# SUSTAINA-SBC-Power-Board.net
KiCad netlist of a schematic drawn in EAGLE
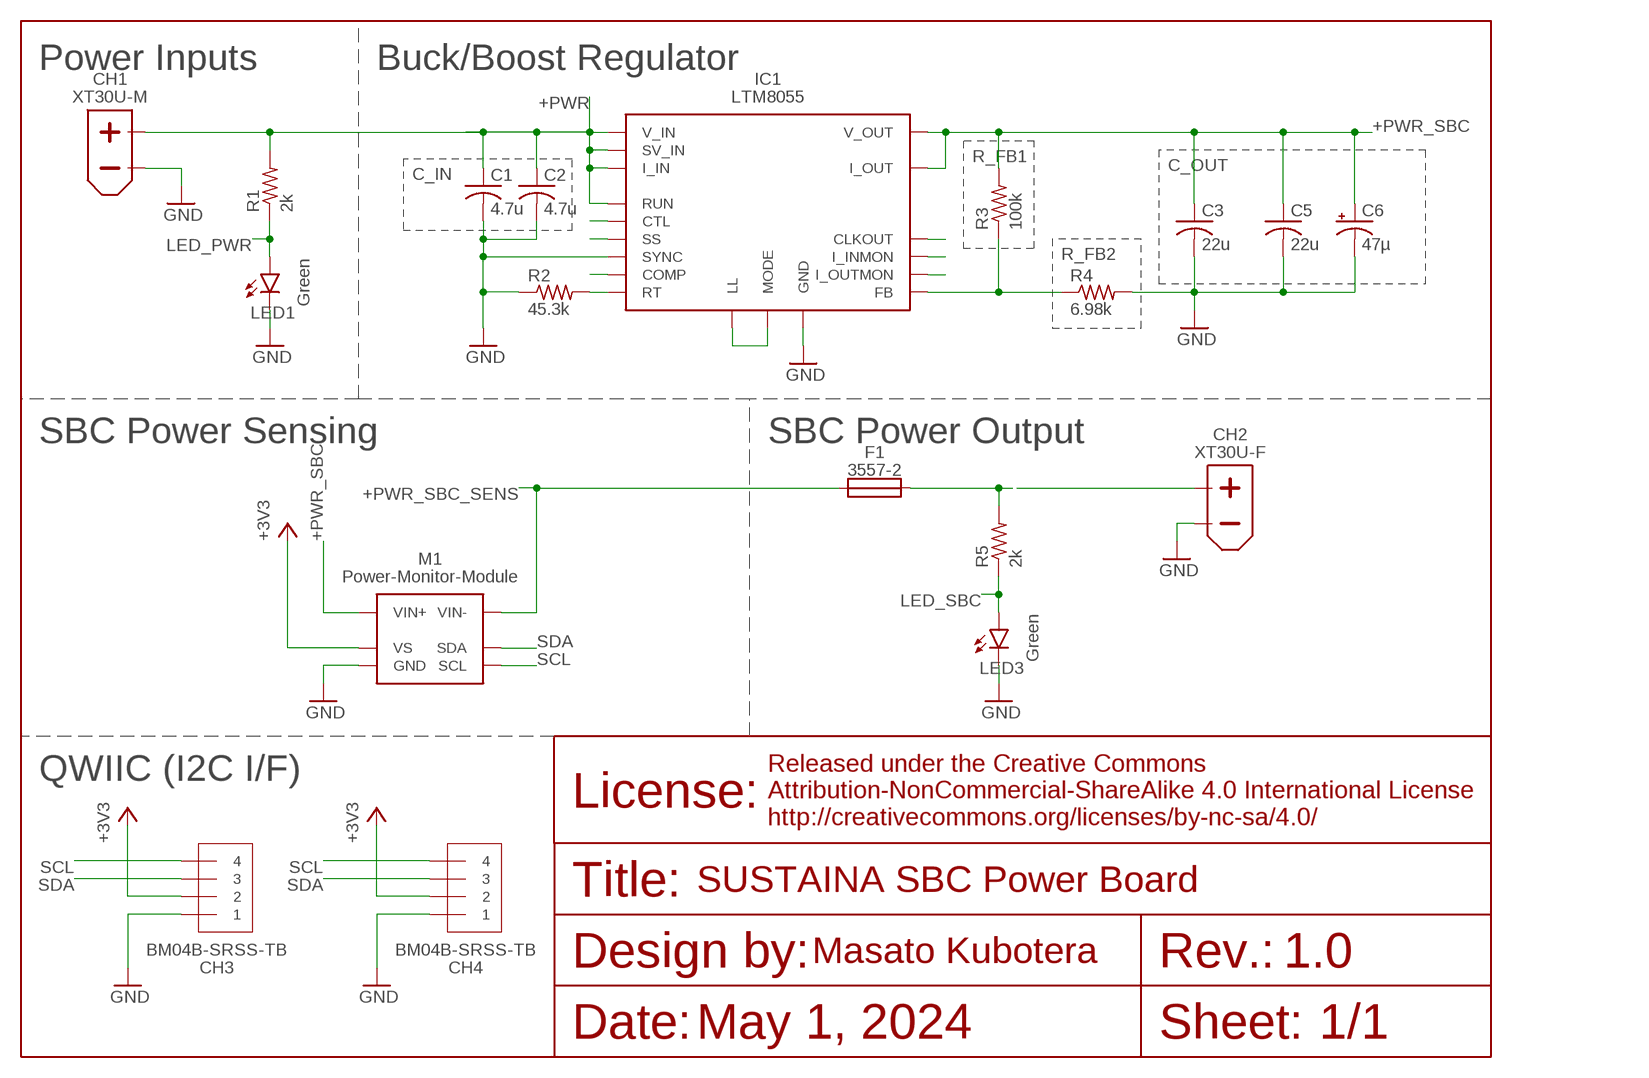
[diagram p0: schematic, sheet 1]

(export (version "E")
  (design (tool "Eeschema 10.0.6"))
  (components
    (comp (ref "C1")
      (value "4.7u")
      (footprint "eagle-import:C0805")
      (libsource (lib "eagle-import") (part "C-USC0805"))
    )
    (comp (ref "C2")
      (value "4.7u")
      (footprint "eagle-import:C0805")
      (libsource (lib "eagle-import") (part "C-USC0805"))
    )
    (comp (ref "C3")
      (value "22u")
      (footprint "eagle-import:C0805")
      (libsource (lib "eagle-import") (part "C-USC0805"))
    )
    (comp (ref "C5")
      (value "22u")
      (footprint "eagle-import:C0805")
      (libsource (lib "eagle-import") (part "C-USC0805"))
    )
    (comp (ref "C6")
      (value "47µ")
      (footprint "eagle-import:D_7343-31R")
      (libsource (lib "eagle-import") (part "CPOL-USD/7343-31R"))
    )
    (comp (ref "CH1")
      (value "XT30U-M")
      (footprint "eagle-import:XT30U-M")
      (libsource (lib "eagle-import") (part "XT30U-M"))
    )
    (comp (ref "CH2")
      (value "XT30U-F")
      (footprint "eagle-import:XT30U-F")
      (libsource (lib "eagle-import") (part "XT30U-F"))
    )
    (comp (ref "CH3")
      (value "BM04B-SRSS-TB")
      (footprint "eagle-import:BM04B-SRSS-TB")
      (libsource (lib "eagle-import") (part "BM04B-SRSS-TB"))
    )
    (comp (ref "CH4")
      (value "BM04B-SRSS-TB")
      (footprint "eagle-import:BM04B-SRSS-TB")
      (libsource (lib "eagle-import") (part "BM04B-SRSS-TB"))
    )
    (comp (ref "F1")
      (value "3557-2")
      (footprint "eagle-import:3557-2")
      (libsource (lib "eagle-import") (part "3557-2"))
    )
    (comp (ref "IC1")
      (value "LTM8055")
      (footprint "eagle-import:LTM8055")
      (libsource (lib "eagle-import") (part "LTM8055"))
    )
    (comp (ref "LED1")
      (value "Green")
      (footprint "eagle-import:SML0603")
      (libsource (lib "eagle-import") (part "LEDSML0603"))
    )
    (comp (ref "LED3")
      (value "Green")
      (footprint "eagle-import:SML0603")
      (libsource (lib "eagle-import") (part "LEDSML0603"))
    )
    (comp (ref "M1")
      (value "POWER-MONITOR-MODULE")
      (footprint "eagle-import:POWER-MONITOR-MODULE")
      (libsource (lib "eagle-import") (part "POWER-MONITOR-MODULE"))
    )
    (comp (ref "R1")
      (value "2k")
      (footprint "eagle-import:R0603")
      (libsource (lib "eagle-import") (part "R-US_R0603"))
    )
    (comp (ref "R2")
      (value "45.3k")
      (footprint "eagle-import:R0603")
      (libsource (lib "eagle-import") (part "R-US_R0603"))
    )
    (comp (ref "R3")
      (value "100k")
      (footprint "eagle-import:R0603")
      (libsource (lib "eagle-import") (part "R-US_R0603"))
    )
    (comp (ref "R4")
      (value "6.98k")
      (footprint "eagle-import:R0603")
      (libsource (lib "eagle-import") (part "R-US_R0603"))
    )
    (comp (ref "R5")
      (value "2k")
      (footprint "eagle-import:R0603")
      (libsource (lib "eagle-import") (part "R-US_R0603"))
    )
  )
  (nets
    (net (code "1") (name "+3V3") (class "Default")
      (node (ref "CH3") (pin "2") (pinfunction "2_2") (pintype "bidirectional"))
      (node (ref "CH4") (pin "2") (pinfunction "2_2") (pintype "bidirectional"))
      (node (ref "M1") (pin "VS") (pinfunction "VS_VS") (pintype "power_in"))
    )
    (net (code "2") (name "/+PWR") (class "Default")
      (node (ref "C1") (pin "1") (pinfunction "1_1") (pintype "passive"))
      (node (ref "C2") (pin "1") (pinfunction "1_1") (pintype "passive"))
      (node (ref "CH1") (pin "+") (pinfunction "+_+") (pintype "power_in"))
      (node (ref "IC1") (pin "F10") (pinfunction "SV_IN_F10") (pintype "bidirectional"))
      (node (ref "IC1") (pin "F11") (pinfunction "SV_IN_F11") (pintype "bidirectional"))
      (node (ref "IC1") (pin "G10") (pinfunction "V_IN_G10") (pintype "bidirectional"))
      (node (ref "IC1") (pin "G11") (pinfunction "V_IN_G11") (pintype "bidirectional"))
      (node (ref "IC1") (pin "H10") (pinfunction "V_IN_H10") (pintype "bidirectional"))
      (node (ref "IC1") (pin "H11") (pinfunction "V_IN_H11") (pintype "bidirectional"))
      (node (ref "IC1") (pin "J10") (pinfunction "V_IN_J10") (pintype "bidirectional"))
      (node (ref "IC1") (pin "J11") (pinfunction "V_IN_J11") (pintype "bidirectional"))
      (node (ref "IC1") (pin "K10") (pinfunction "V_IN_K10") (pintype "bidirectional"))
      (node (ref "IC1") (pin "K11") (pinfunction "V_IN_K11") (pintype "bidirectional"))
      (node (ref "IC1") (pin "L10") (pinfunction "V_IN_L10") (pintype "bidirectional"))
      (node (ref "IC1") (pin "L11") (pinfunction "V_IN_L11") (pintype "bidirectional"))
      (node (ref "IC1") (pin "L4") (pinfunction "RUN_L4") (pintype "bidirectional"))
      (node (ref "IC1") (pin "L9") (pinfunction "I_IN_L9") (pintype "bidirectional"))
      (node (ref "R1") (pin "2") (pinfunction "2_2") (pintype "passive"))
    )
    (net (code "3") (name "/+PWR_SBC") (class "Default")
      (node (ref "C3") (pin "1") (pinfunction "1_1") (pintype "passive"))
      (node (ref "C5") (pin "1") (pinfunction "1_1") (pintype "passive"))
      (node (ref "C6") (pin "+") (pinfunction "+_+") (pintype "passive"))
      (node (ref "IC1") (pin "A1") (pinfunction "V_OUT_A1") (pintype "bidirectional"))
      (node (ref "IC1") (pin "A2") (pinfunction "V_OUT_A2") (pintype "bidirectional"))
      (node (ref "IC1") (pin "A3") (pinfunction "V_OUT_A3") (pintype "bidirectional"))
      (node (ref "IC1") (pin "A4") (pinfunction "V_OUT_A4") (pintype "bidirectional"))
      (node (ref "IC1") (pin "A5") (pinfunction "V_OUT_A5") (pintype "bidirectional"))
      (node (ref "IC1") (pin "A6") (pinfunction "V_OUT_A6") (pintype "bidirectional"))
      (node (ref "IC1") (pin "B1") (pinfunction "V_OUT_B1") (pintype "bidirectional"))
      (node (ref "IC1") (pin "B2") (pinfunction "V_OUT_B2") (pintype "bidirectional"))
      (node (ref "IC1") (pin "B3") (pinfunction "V_OUT_B3") (pintype "bidirectional"))
      (node (ref "IC1") (pin "B4") (pinfunction "V_OUT_B4") (pintype "bidirectional"))
      (node (ref "IC1") (pin "B5") (pinfunction "V_OUT_B5") (pintype "bidirectional"))
      (node (ref "IC1") (pin "B6") (pinfunction "V_OUT_B6") (pintype "bidirectional"))
      (node (ref "IC1") (pin "C1") (pinfunction "V_OUT_C1") (pintype "bidirectional"))
      (node (ref "IC1") (pin "C2") (pinfunction "V_OUT_C2") (pintype "bidirectional"))
      (node (ref "IC1") (pin "C3") (pinfunction "V_OUT_C3") (pintype "bidirectional"))
      (node (ref "IC1") (pin "C4") (pinfunction "V_OUT_C4") (pintype "bidirectional"))
      (node (ref "IC1") (pin "C5") (pinfunction "V_OUT_C5") (pintype "bidirectional"))
      (node (ref "IC1") (pin "C6") (pinfunction "V_OUT_C6") (pintype "bidirectional"))
      (node (ref "IC1") (pin "D1") (pinfunction "I_OUT_D1") (pintype "bidirectional"))
      (node (ref "M1") (pin "VIN+1") (pinfunction "VIN+_VIN+1") (pintype "power_in"))
      (node (ref "M1") (pin "VIN+10") (pinfunction "VIN+_VIN+10") (pintype "power_in"))
      (node (ref "M1") (pin "VIN+2") (pinfunction "VIN+_VIN+2") (pintype "power_in"))
      (node (ref "M1") (pin "VIN+3") (pinfunction "VIN+_VIN+3") (pintype "power_in"))
      (node (ref "M1") (pin "VIN+4") (pinfunction "VIN+_VIN+4") (pintype "power_in"))
      (node (ref "M1") (pin "VIN+5") (pinfunction "VIN+_VIN+5") (pintype "power_in"))
      (node (ref "M1") (pin "VIN+6") (pinfunction "VIN+_VIN+6") (pintype "power_in"))
      (node (ref "M1") (pin "VIN+7") (pinfunction "VIN+_VIN+7") (pintype "power_in"))
      (node (ref "M1") (pin "VIN+8") (pinfunction "VIN+_VIN+8") (pintype "power_in"))
      (node (ref "M1") (pin "VIN+9") (pinfunction "VIN+_VIN+9") (pintype "power_in"))
      (node (ref "R3") (pin "2") (pinfunction "2_2") (pintype "passive"))
    )
    (net (code "4") (name "/+PWR_SBC_SENS") (class "Default")
      (node (ref "F1") (pin "1") (pinfunction "1_1") (pintype "bidirectional"))
      (node (ref "F1") (pin "2") (pinfunction "1_2") (pintype "bidirectional"))
      (node (ref "M1") (pin "VIN-1") (pinfunction "VIN-_VIN-1") (pintype "power_in"))
      (node (ref "M1") (pin "VIN-10") (pinfunction "VIN-_VIN-10") (pintype "power_in"))
      (node (ref "M1") (pin "VIN-2") (pinfunction "VIN-_VIN-2") (pintype "power_in"))
      (node (ref "M1") (pin "VIN-3") (pinfunction "VIN-_VIN-3") (pintype "power_in"))
      (node (ref "M1") (pin "VIN-4") (pinfunction "VIN-_VIN-4") (pintype "power_in"))
      (node (ref "M1") (pin "VIN-5") (pinfunction "VIN-_VIN-5") (pintype "power_in"))
      (node (ref "M1") (pin "VIN-6") (pinfunction "VIN-_VIN-6") (pintype "power_in"))
      (node (ref "M1") (pin "VIN-7") (pinfunction "VIN-_VIN-7") (pintype "power_in"))
      (node (ref "M1") (pin "VIN-8") (pinfunction "VIN-_VIN-8") (pintype "power_in"))
      (node (ref "M1") (pin "VIN-9") (pinfunction "VIN-_VIN-9") (pintype "power_in"))
    )
    (net (code "5") (name "/LED_PWR") (class "Default")
      (node (ref "LED1") (pin "A") (pinfunction "A_A") (pintype "passive"))
      (node (ref "R1") (pin "1") (pinfunction "1_1") (pintype "passive"))
    )
    (net (code "6") (name "/LED_SBC") (class "Default")
      (node (ref "LED3") (pin "A") (pinfunction "A_A") (pintype "passive"))
      (node (ref "R5") (pin "1") (pinfunction "1_1") (pintype "passive"))
    )
    (net (code "7") (name "/SCL") (class "Default")
      (node (ref "CH3") (pin "4") (pinfunction "4_4") (pintype "bidirectional"))
      (node (ref "CH4") (pin "4") (pinfunction "4_4") (pintype "bidirectional"))
      (node (ref "M1") (pin "SCL") (pinfunction "SCL_SCL") (pintype "bidirectional"))
    )
    (net (code "8") (name "/SDA") (class "Default")
      (node (ref "CH3") (pin "3") (pinfunction "3_3") (pintype "bidirectional"))
      (node (ref "CH4") (pin "3") (pinfunction "3_3") (pintype "bidirectional"))
      (node (ref "M1") (pin "SDA") (pinfunction "SDA_SDA") (pintype "bidirectional"))
    )
    (net (code "9") (name "GND") (class "Default")
      (node (ref "C1") (pin "2") (pinfunction "2_2") (pintype "passive"))
      (node (ref "C2") (pin "2") (pinfunction "2_2") (pintype "passive"))
      (node (ref "C3") (pin "2") (pinfunction "2_2") (pintype "passive"))
      (node (ref "C5") (pin "2") (pinfunction "2_2") (pintype "passive"))
      (node (ref "C6") (pin "-") (pinfunction "-_-") (pintype "passive"))
      (node (ref "CH1") (pin "-") (pinfunction "-_-") (pintype "power_in"))
      (node (ref "CH2") (pin "-") (pinfunction "-_-") (pintype "power_in"))
      (node (ref "CH3") (pin "1") (pinfunction "1_1") (pintype "bidirectional"))
      (node (ref "CH4") (pin "1") (pinfunction "1_1") (pintype "bidirectional"))
      (node (ref "IC1") (pin "A10") (pinfunction "GND_A10") (pintype "bidirectional"))
      (node (ref "IC1") (pin "A11") (pinfunction "GND_A11") (pintype "bidirectional"))
      (node (ref "IC1") (pin "A7") (pinfunction "GND_A7") (pintype "bidirectional"))
      (node (ref "IC1") (pin "A8") (pinfunction "GND_A8") (pintype "bidirectional"))
      (node (ref "IC1") (pin "A9") (pinfunction "GND_A9") (pintype "bidirectional"))
      (node (ref "IC1") (pin "B10") (pinfunction "GND_B10") (pintype "bidirectional"))
      (node (ref "IC1") (pin "B11") (pinfunction "GND_B11") (pintype "bidirectional"))
      (node (ref "IC1") (pin "B7") (pinfunction "GND_B7") (pintype "bidirectional"))
      (node (ref "IC1") (pin "B8") (pinfunction "GND_B8") (pintype "bidirectional"))
      (node (ref "IC1") (pin "B9") (pinfunction "GND_B9") (pintype "bidirectional"))
      (node (ref "IC1") (pin "C10") (pinfunction "GND_C10") (pintype "bidirectional"))
      (node (ref "IC1") (pin "C11") (pinfunction "GND_C11") (pintype "bidirectional"))
      (node (ref "IC1") (pin "C7") (pinfunction "GND_C7") (pintype "bidirectional"))
      (node (ref "IC1") (pin "C8") (pinfunction "GND_C8") (pintype "bidirectional"))
      (node (ref "IC1") (pin "C9") (pinfunction "GND_C9") (pintype "bidirectional"))
      (node (ref "IC1") (pin "D10") (pinfunction "GND_D10") (pintype "bidirectional"))
      (node (ref "IC1") (pin "D11") (pinfunction "GND_D11") (pintype "bidirectional"))
      (node (ref "IC1") (pin "D2") (pinfunction "GND_D2") (pintype "bidirectional"))
      (node (ref "IC1") (pin "D3") (pinfunction "GND_D3") (pintype "bidirectional"))
      (node (ref "IC1") (pin "D4") (pinfunction "GND_D4") (pintype "bidirectional"))
      (node (ref "IC1") (pin "D5") (pinfunction "GND_D5") (pintype "bidirectional"))
      (node (ref "IC1") (pin "D6") (pinfunction "GND_D6") (pintype "bidirectional"))
      (node (ref "IC1") (pin "D7") (pinfunction "GND_D7") (pintype "bidirectional"))
      (node (ref "IC1") (pin "D8") (pinfunction "GND_D8") (pintype "bidirectional"))
      (node (ref "IC1") (pin "D9") (pinfunction "GND_D9") (pintype "bidirectional"))
      (node (ref "IC1") (pin "E1") (pinfunction "GND_E1") (pintype "bidirectional"))
      (node (ref "IC1") (pin "E10") (pinfunction "GND_E10") (pintype "bidirectional"))
      (node (ref "IC1") (pin "E11") (pinfunction "GND_E11") (pintype "bidirectional"))
      (node (ref "IC1") (pin "E2") (pinfunction "GND_E2") (pintype "bidirectional"))
      (node (ref "IC1") (pin "E3") (pinfunction "GND_E3") (pintype "bidirectional"))
      (node (ref "IC1") (pin "E4") (pinfunction "GND_E4") (pintype "bidirectional"))
      (node (ref "IC1") (pin "E5") (pinfunction "GND_E5") (pintype "bidirectional"))
      (node (ref "IC1") (pin "E6") (pinfunction "GND_E6") (pintype "bidirectional"))
      (node (ref "IC1") (pin "E7") (pinfunction "GND_E7") (pintype "bidirectional"))
      (node (ref "IC1") (pin "E8") (pinfunction "GND_E8") (pintype "bidirectional"))
      (node (ref "IC1") (pin "E9") (pinfunction "GND_E9") (pintype "bidirectional"))
      (node (ref "IC1") (pin "F2") (pinfunction "GND_F2") (pintype "bidirectional"))
      (node (ref "IC1") (pin "F3") (pinfunction "GND_F3") (pintype "bidirectional"))
      (node (ref "IC1") (pin "F4") (pinfunction "GND_F4") (pintype "bidirectional"))
      (node (ref "IC1") (pin "F5") (pinfunction "GND_F5") (pintype "bidirectional"))
      (node (ref "IC1") (pin "F6") (pinfunction "GND_F6") (pintype "bidirectional"))
      (node (ref "IC1") (pin "F7") (pinfunction "GND_F7") (pintype "bidirectional"))
      (node (ref "IC1") (pin "F8") (pinfunction "GND_F8") (pintype "bidirectional"))
      (node (ref "IC1") (pin "F9") (pinfunction "GND_F9") (pintype "bidirectional"))
      (node (ref "IC1") (pin "G3") (pinfunction "GND_G3") (pintype "bidirectional"))
      (node (ref "IC1") (pin "G4") (pinfunction "GND_G4") (pintype "bidirectional"))
      (node (ref "IC1") (pin "G5") (pinfunction "GND_G5") (pintype "bidirectional"))
      (node (ref "IC1") (pin "G6") (pinfunction "GND_G6") (pintype "bidirectional"))
      (node (ref "IC1") (pin "G7") (pinfunction "GND_G7") (pintype "bidirectional"))
      (node (ref "IC1") (pin "G8") (pinfunction "GND_G8") (pintype "bidirectional"))
      (node (ref "IC1") (pin "G9") (pinfunction "GND_G9") (pintype "bidirectional"))
      (node (ref "IC1") (pin "H2") (pinfunction "SYNC_H2") (pintype "bidirectional"))
      (node (ref "IC1") (pin "H3") (pinfunction "GND_H3") (pintype "bidirectional"))
      (node (ref "IC1") (pin "H4") (pinfunction "GND_H4") (pintype "bidirectional"))
      (node (ref "IC1") (pin "H5") (pinfunction "GND_H5") (pintype "bidirectional"))
      (node (ref "IC1") (pin "H6") (pinfunction "GND_H6") (pintype "bidirectional"))
      (node (ref "IC1") (pin "H7") (pinfunction "GND_H7") (pintype "bidirectional"))
      (node (ref "IC1") (pin "H8") (pinfunction "GND_H8") (pintype "bidirectional"))
      (node (ref "IC1") (pin "H9") (pinfunction "GND_H9") (pintype "bidirectional"))
      (node (ref "IC1") (pin "J3") (pinfunction "GND_J3") (pintype "bidirectional"))
      (node (ref "IC1") (pin "J4") (pinfunction "GND_J4") (pintype "bidirectional"))
      (node (ref "IC1") (pin "J5") (pinfunction "GND_J5") (pintype "bidirectional"))
      (node (ref "IC1") (pin "J6") (pinfunction "GND_J6") (pintype "bidirectional"))
      (node (ref "IC1") (pin "J7") (pinfunction "GND_J7") (pintype "bidirectional"))
      (node (ref "IC1") (pin "J8") (pinfunction "GND_J8") (pintype "bidirectional"))
      (node (ref "IC1") (pin "J9") (pinfunction "GND_J9") (pintype "bidirectional"))
      (node (ref "IC1") (pin "K3") (pinfunction "GND_K3") (pintype "bidirectional"))
      (node (ref "IC1") (pin "K4") (pinfunction "GND_K4") (pintype "bidirectional"))
      (node (ref "IC1") (pin "K5") (pinfunction "GND_K5") (pintype "bidirectional"))
      (node (ref "IC1") (pin "K6") (pinfunction "GND_K6") (pintype "bidirectional"))
      (node (ref "IC1") (pin "K7") (pinfunction "GND_K7") (pintype "bidirectional"))
      (node (ref "IC1") (pin "K8") (pinfunction "GND_K8") (pintype "bidirectional"))
      (node (ref "IC1") (pin "K9") (pinfunction "GND_K9") (pintype "bidirectional"))
      (node (ref "IC1") (pin "L1") (pinfunction "GND_L1") (pintype "bidirectional"))
      (node (ref "IC1") (pin "L5") (pinfunction "GND_L5") (pintype "bidirectional"))
      (node (ref "IC1") (pin "L6") (pinfunction "GND_L6") (pintype "bidirectional"))
      (node (ref "IC1") (pin "L7") (pinfunction "GND_L7") (pintype "bidirectional"))
      (node (ref "IC1") (pin "L8") (pinfunction "GND_L8") (pintype "bidirectional"))
      (node (ref "LED1") (pin "C") (pinfunction "C_C") (pintype "passive"))
      (node (ref "LED3") (pin "C") (pinfunction "C_C") (pintype "passive"))
      (node (ref "M1") (pin "GND") (pinfunction "GND_GND") (pintype "power_in"))
      (node (ref "R2") (pin "1") (pinfunction "1_1") (pintype "passive"))
      (node (ref "R4") (pin "2") (pinfunction "2_2") (pintype "passive"))
    )
    (net (code "10") (name "Net-(CH2-Pad+)") (class "Default")
      (node (ref "CH2") (pin "+") (pinfunction "+_+") (pintype "power_in"))
      (node (ref "F1") (pin "3") (pinfunction "2_3") (pintype "bidirectional"))
      (node (ref "F1") (pin "4") (pinfunction "2_4") (pintype "bidirectional"))
      (node (ref "R5") (pin "2") (pinfunction "2_2") (pintype "passive"))
    )
    (net (code "11") (name "Net-(IC1-FB)") (class "Default")
      (node (ref "IC1") (pin "J1") (pinfunction "FB_J1") (pintype "bidirectional"))
      (node (ref "R3") (pin "1") (pinfunction "1_1") (pintype "passive"))
      (node (ref "R4") (pin "1") (pinfunction "1_1") (pintype "passive"))
    )
    (net (code "12") (name "Net-(IC1-LL)") (class "Default")
      (node (ref "IC1") (pin "F1") (pinfunction "LL_F1") (pintype "bidirectional"))
      (node (ref "IC1") (pin "G2") (pinfunction "MODE_G2") (pintype "bidirectional"))
    )
    (net (code "13") (name "Net-(IC1-RT)") (class "Default")
      (node (ref "IC1") (pin "H1") (pinfunction "RT_H1") (pintype "bidirectional"))
      (node (ref "R2") (pin "2") (pinfunction "2_2") (pintype "passive"))
    )
    (net (code "14") (name "unconnected-(IC1-CLKOUT-PadG1)") (class "Default")
      (node (ref "IC1") (pin "G1") (pinfunction "CLKOUT_G1") (pintype "bidirectional"))
    )
    (net (code "15") (name "unconnected-(IC1-COMP-PadJ2)") (class "Default")
      (node (ref "IC1") (pin "J2") (pinfunction "COMP_J2") (pintype "bidirectional"))
    )
    (net (code "16") (name "unconnected-(IC1-CTL-PadK2)") (class "Default")
      (node (ref "IC1") (pin "K2") (pinfunction "CTL_K2") (pintype "bidirectional"))
    )
    (net (code "17") (name "unconnected-(IC1-I_INMON-PadL3)") (class "Default")
      (node (ref "IC1") (pin "L3") (pinfunction "I_INMON_L3") (pintype "bidirectional"))
    )
    (net (code "18") (name "unconnected-(IC1-I_OUTMON-PadL2)") (class "Default")
      (node (ref "IC1") (pin "L2") (pinfunction "I_OUTMON_L2") (pintype "bidirectional"))
    )
    (net (code "19") (name "unconnected-(IC1-SS-PadK1)") (class "Default")
      (node (ref "IC1") (pin "K1") (pinfunction "SS_K1") (pintype "bidirectional"))
    )
  )
)
